# Lasersch.net
KiCad netlist of a schematic drawn in Altium Designer
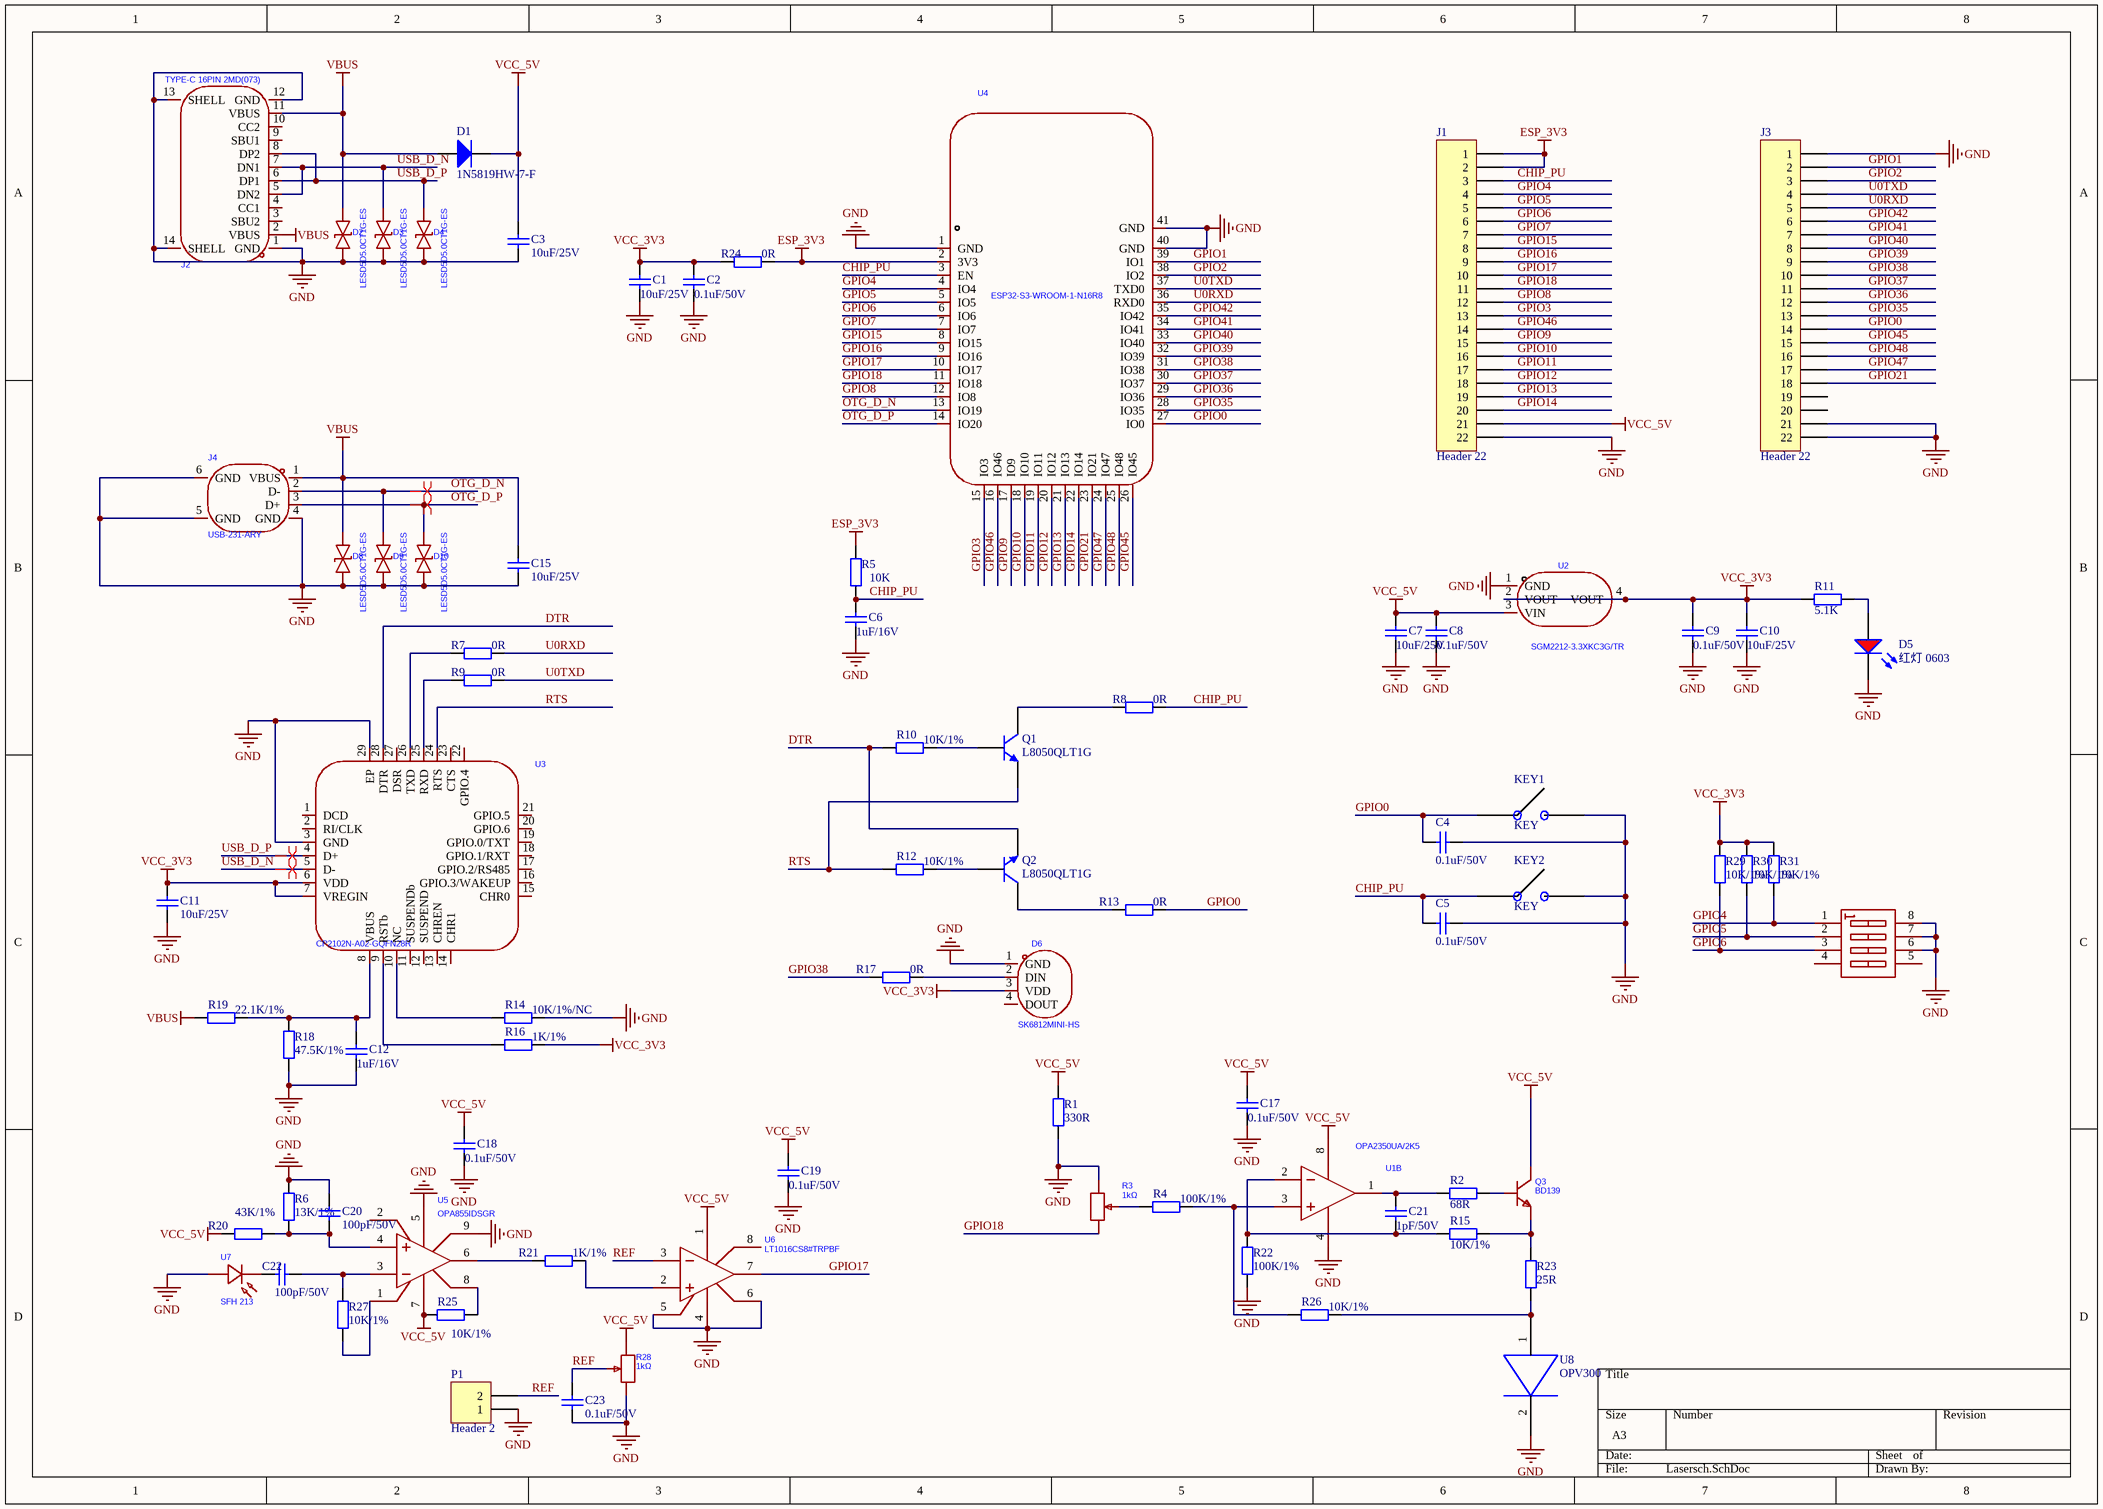
[diagram p0: Lasersch.SchDoc]

(export (version "E")
  (design (tool "Eeschema 10.0.6"))
  (components
    (comp (ref "C1")
      (value "10uF/25V")
      (footprint "0805_C")
      (description "贴片电容")
      (libsource (lib "Cap") (part "0805 2.0pF (2R0) 0.25pF 50V"))
    )
    (comp (ref "C2")
      (value "0.1uF/50V")
      (footprint "0603_C")
      (description "贴片电容")
      (libsource (lib "Cap") (part "0603 8.2nF (822) 10% 50V"))
    )
    (comp (ref "C3")
      (value "10uF/25V")
      (footprint "0805_C")
      (description "贴片电容")
      (libsource (lib "Cap") (part "0805 2.0pF (2R0) 0.25pF 50V"))
    )
    (comp (ref "C4")
      (value "0.1uF/50V")
      (footprint "0603_C")
      (description "贴片电容")
      (libsource (lib "Cap") (part "0603 8.2nF (822) 10% 50V"))
    )
    (comp (ref "C5")
      (value "0.1uF/50V")
      (footprint "0603_C")
      (description "贴片电容")
      (libsource (lib "Cap") (part "0603 8.2nF (822) 10% 50V"))
    )
    (comp (ref "C6")
      (value "1uF/16V")
      (footprint "0603_C")
      (description "贴片电容")
      (libsource (lib "Cap") (part "0603 8.2nF (822) 10% 50V"))
    )
    (comp (ref "C7")
      (value "10uF/25V")
      (footprint "0805_C")
      (description "贴片电容")
      (libsource (lib "Cap") (part "0805 2.0pF (2R0) 0.25pF 50V"))
    )
    (comp (ref "C8")
      (value "0.1uF/50V")
      (footprint "0603_C")
      (description "贴片电容")
      (libsource (lib "Cap") (part "0603 8.2nF (822) 10% 50V"))
    )
    (comp (ref "C9")
      (value "0.1uF/50V")
      (footprint "0603_C")
      (description "贴片电容")
      (libsource (lib "Cap") (part "0603 8.2nF (822) 10% 50V"))
    )
    (comp (ref "C10")
      (value "10uF/25V")
      (footprint "0805_C")
      (description "贴片电容")
      (libsource (lib "Cap") (part "0805 2.0pF (2R0) 0.25pF 50V"))
    )
    (comp (ref "C11")
      (value "10uF/25V")
      (footprint "0805_C")
      (description "贴片电容")
      (libsource (lib "Cap") (part "0805 2.0pF (2R0) 0.25pF 50V"))
    )
    (comp (ref "C12")
      (value "1uF/16V")
      (footprint "0603_C")
      (description "贴片电容")
      (libsource (lib "Cap") (part "0603 8.2nF (822) 10% 50V"))
    )
    (comp (ref "C15")
      (value "10uF/25V")
      (footprint "0805_C")
      (description "贴片电容")
      (libsource (lib "Cap") (part "0805 2.0pF (2R0) 0.25pF 50V"))
    )
    (comp (ref "C17")
      (value "0.1uF/50V")
      (footprint "0603_C")
      (description "贴片电容")
      (libsource (lib "Cap") (part "0603 8.2nF (822) 10% 50V"))
    )
    (comp (ref "C18")
      (value "0.1uF/50V")
      (footprint "0603_C")
      (description "贴片电容")
      (libsource (lib "Cap") (part "0603 8.2nF (822) 10% 50V"))
    )
    (comp (ref "C19")
      (value "0.1uF/50V")
      (footprint "0603_C")
      (description "贴片电容")
      (libsource (lib "Cap") (part "0603 8.2nF (822) 10% 50V"))
    )
    (comp (ref "C20")
      (value "100pF/50V")
      (footprint "0603_C")
      (description "贴片电容")
      (libsource (lib "Cap") (part "0603 8.2nF (822) 10% 50V"))
    )
    (comp (ref "C21")
      (value "1pF/50V")
      (footprint "0603_C")
      (description "贴片电容")
      (libsource (lib "Cap") (part "0603 8.2nF (822) 10% 50V"))
    )
    (comp (ref "C22")
      (value "100pF/50V")
      (footprint "0603_C")
      (description "贴片电容")
      (libsource (lib "Cap") (part "0603 8.2nF (822) 10% 50V"))
    )
    (comp (ref "C23")
      (value "0.1uF/50V")
      (footprint "0603_C")
      (description "贴片电容")
      (libsource (lib "Cap") (part "0603 8.2nF (822) 10% 50V"))
    )
    (comp (ref "D1")
      (value "1N5819HW-7-F")
      (footprint "SOD-123")
      (description "射频开关二极管")
      (libsource (lib "Diode") (part "1SS314"))
    )
    (comp (ref "D2")
      (value "LESD5D5.0CT1G-ES")
      (footprint "SOD-523_L1.2-W0.8-LS1.6-BI")
      (fields (field (name "MANUFACTURER") "ElecSuper(静芯微)"))
      (libsource (lib "电源板") (part "LESD5D5.0CT1G-ES"))
    )
    (comp (ref "D3")
      (value "LESD5D5.0CT1G-ES")
      (footprint "SOD-523_L1.2-W0.8-LS1.6-BI")
      (fields (field (name "MANUFACTURER") "ElecSuper(静芯微)"))
      (libsource (lib "电源板") (part "LESD5D5.0CT1G-ES"))
    )
    (comp (ref "D4")
      (value "LESD5D5.0CT1G-ES")
      (footprint "SOD-523_L1.2-W0.8-LS1.6-BI")
      (fields (field (name "MANUFACTURER") "ElecSuper(静芯微)"))
      (libsource (lib "电源板") (part "LESD5D5.0CT1G-ES"))
    )
    (comp (ref "D5")
      (value "红灯 0603")
      (footprint "0603_LED_S1")
      (description "发光二极管")
      (libsource (lib "LED") (part "0603 红灯"))
    )
    (comp (ref "D6")
      (value "SK6812MINI-HS")
      (footprint "LED-SMD_4P-L3.5-W3.5-BR_SK6812MINI-HS")
      (fields (field (name "MANUFACTURER") "欧思科光电"))
      (libsource (lib "电源板") (part "SK6812MINI-HS"))
    )
    (comp (ref "D8")
      (value "LESD5D5.0CT1G-ES")
      (footprint "SOD-523_L1.2-W0.8-LS1.6-BI")
      (fields (field (name "MANUFACTURER") "ElecSuper(静芯微)"))
      (libsource (lib "电源板") (part "LESD5D5.0CT1G-ES"))
    )
    (comp (ref "D9")
      (value "LESD5D5.0CT1G-ES")
      (footprint "SOD-523_L1.2-W0.8-LS1.6-BI")
      (fields (field (name "MANUFACTURER") "ElecSuper(静芯微)"))
      (libsource (lib "电源板") (part "LESD5D5.0CT1G-ES"))
    )
    (comp (ref "D10")
      (value "LESD5D5.0CT1G-ES")
      (footprint "SOD-523_L1.2-W0.8-LS1.6-BI")
      (fields (field (name "MANUFACTURER") "ElecSuper(静芯微)"))
      (libsource (lib "电源板") (part "LESD5D5.0CT1G-ES"))
    )
    (comp (ref "J1")
      (value "Header 22")
      (footprint "HDR1X22")
      (description "Header, 22-Pin")
      (fields (field (name "PUBLISHER") "Altium Limited"))
      (libsource (lib "Miscellaneous Connectors") (part "Header 22"))
    )
    (comp (ref "J2")
      (value "TYPE-C 16PIN 2MD(073)")
      (footprint "USB-C-SMD_TYPE-C-6PIN-2MD-073")
      (fields (field (name "MANUFACTURER") "SHOU HAN(首韩)"))
      (libsource (lib "电源板") (part "TYPE-C 16PIN 2MD(073)"))
    )
    (comp (ref "J3")
      (value "Header 22")
      (footprint "HDR1X22")
      (description "Header, 22-Pin")
      (fields (field (name "PUBLISHER") "Altium Limited"))
      (libsource (lib "Miscellaneous Connectors") (part "Header 22"))
    )
    (comp (ref "J4")
      (value "USB-231-ARY")
      (footprint "USB-A-TH_USB-231-ARY")
      (fields (field (name "MANUFACTURER") "XUNPU(讯普)"))
      (libsource (lib "电源板") (part "USB-231-ARY"))
    )
    (comp (ref "KEY1") (value "KEY") (footprint "SW-smt") (libsource (lib "My Device") (part "keysmt")))
    (comp (ref "KEY2") (value "KEY") (footprint "SW-smt") (libsource (lib "My Device") (part "keysmt")))
    (comp (ref "P1")
      (value "Header 2")
      (footprint "HDR1X2")
      (description "Header, 2-Pin")
      (fields (field (name "PUBLISHER") "Altium Limited"))
      (libsource (lib "Miscellaneous Connectors") (part "Header 2"))
    )
    (comp (ref "Q1")
      (value "L8050QLT1G")
      (footprint "SOT-23(SOT-23-3)")
      (description "三极管")
      (libsource (lib "Transistor_NPN") (part "SOT-23 MMBT5551  G1"))
    )
    (comp (ref "Q2")
      (value "L8050QLT1G")
      (footprint "SOT-23(SOT-23-3)")
      (description "三极管")
      (libsource (lib "Transistor_NPN") (part "SOT-23 MMBT5551  G1"))
    )
    (comp (ref "Q3")
      (value "BD139")
      (footprint "TO-126_L7.5-W2.5-P2.3-B")
      (fields (field (name "MANUFACTURER") "ST(意法半导体)"))
      (libsource (lib "电源板") (part "BD139"))
    )
    (comp (ref "R1")
      (value "330R")
      (footprint "0603_R")
      (description "贴片电阻")
      (libsource (lib "RES") (part "0603 1KΩ (1001) 1%"))
    )
    (comp (ref "R2")
      (value "68R")
      (footprint "0603_R")
      (description "贴片电阻")
      (libsource (lib "") (part "0603 1KΩ (1001) 1%_3"))
    )
    (comp (ref "R3")
      (value "1kΩ")
      (footprint "RES-ADJ-TH_3296W")
      (fields
        (field (name "MANUFACTURER") "BOURNS")
        (field (name "MANUFACTURER PART") "3296W-1-102LF")
        (field (name "TOLERANCE") "±10%")
      )
      (libsource (lib "电源板") (part "3296W-1-102LF"))
    )
    (comp (ref "R4")
      (value "100K/1%")
      (footprint "0603_R")
      (description "贴片电阻")
      (libsource (lib "") (part "0603 1KΩ (1001) 1%_1"))
    )
    (comp (ref "R5")
      (value "10K")
      (footprint "0603_R")
      (description "贴片电阻")
      (libsource (lib "RES") (part "0603 1KΩ (1001) 1%"))
    )
    (comp (ref "R6")
      (value "13K/1%")
      (footprint "0603_R")
      (description "贴片电阻")
      (libsource (lib "RES") (part "0603 1KΩ (1001) 1%"))
    )
    (comp (ref "R7")
      (value "0R")
      (footprint "0603_R")
      (description "贴片电阻")
      (libsource (lib "") (part "0603 1KΩ (1001) 1%_1"))
    )
    (comp (ref "R8")
      (value "0R")
      (footprint "0603_R")
      (description "贴片电阻")
      (libsource (lib "") (part "0603 1KΩ (1001) 1%_1"))
    )
    (comp (ref "R9")
      (value "0R")
      (footprint "0603_R")
      (description "贴片电阻")
      (libsource (lib "") (part "0603 1KΩ (1001) 1%_1"))
    )
    (comp (ref "R10")
      (value "10K/1%")
      (footprint "0603_R")
      (description "贴片电阻")
      (libsource (lib "") (part "0603 1KΩ (1001) 1%_1"))
    )
    (comp (ref "R11")
      (value "5.1K")
      (footprint "0603_R")
      (description "贴片电阻")
      (libsource (lib "") (part "0603 1KΩ (1001) 1%_3"))
    )
    (comp (ref "R12")
      (value "10K/1%")
      (footprint "0603_R")
      (description "贴片电阻")
      (libsource (lib "") (part "0603 1KΩ (1001) 1%_1"))
    )
    (comp (ref "R13")
      (value "0R")
      (footprint "0603_R")
      (description "贴片电阻")
      (libsource (lib "") (part "0603 1KΩ (1001) 1%_1"))
    )
    (comp (ref "R14")
      (value "10K/1%/NC")
      (footprint "0603_R")
      (description "贴片电阻")
      (libsource (lib "") (part "0603 1KΩ (1001) 1%_1"))
    )
    (comp (ref "R15")
      (value "10K/1%")
      (footprint "0603_R")
      (description "贴片电阻")
      (libsource (lib "") (part "0603 1KΩ (1001) 1%_3"))
    )
    (comp (ref "R16")
      (value "1K/1%")
      (footprint "0603_R")
      (description "贴片电阻")
      (libsource (lib "") (part "0603 1KΩ (1001) 1%_1"))
    )
    (comp (ref "R17")
      (value "0R")
      (footprint "0603_R")
      (description "贴片电阻")
      (libsource (lib "") (part "0603 1KΩ (1001) 1%_1"))
    )
    (comp (ref "R18")
      (value "47.5K/1%")
      (footprint "0603_R")
      (description "贴片电阻")
      (libsource (lib "RES") (part "0603 1KΩ (1001) 1%"))
    )
    (comp (ref "R19")
      (value "22.1K/1%")
      (footprint "0603_R")
      (description "贴片电阻")
      (libsource (lib "") (part "0603 1KΩ (1001) 1%_1"))
    )
    (comp (ref "R20")
      (value "43K/1%")
      (footprint "0603_R")
      (description "贴片电阻")
      (libsource (lib "") (part "0603 1KΩ (1001) 1%_1"))
    )
    (comp (ref "R21")
      (value "1K/1%")
      (footprint "0603_R")
      (description "贴片电阻")
      (libsource (lib "") (part "0603 1KΩ (1001) 1%_1"))
    )
    (comp (ref "R22")
      (value "100K/1%")
      (footprint "0603_R")
      (description "贴片电阻")
      (libsource (lib "") (part "0603 1KΩ (1001) 1%_2"))
    )
    (comp (ref "R23")
      (value "25R")
      (footprint "0603_R")
      (description "贴片电阻")
      (libsource (lib "") (part "0603 1KΩ (1001) 1%_2"))
    )
    (comp (ref "R24")
      (value "0R")
      (footprint "0603_R")
      (description "贴片电阻")
      (libsource (lib "") (part "0603 1KΩ (1001) 1%_1"))
    )
    (comp (ref "R25")
      (value "10K/1%")
      (footprint "0603_R")
      (description "贴片电阻")
      (libsource (lib "") (part "0603 1KΩ (1001) 1%_1"))
    )
    (comp (ref "R26")
      (value "10K/1%")
      (footprint "0603_R")
      (description "贴片电阻")
      (libsource (lib "") (part "0603 1KΩ (1001) 1%_1"))
    )
    (comp (ref "R27")
      (value "10K/1%")
      (footprint "0603_R")
      (description "贴片电阻")
      (libsource (lib "RES") (part "0603 1KΩ (1001) 1%"))
    )
    (comp (ref "R28")
      (value "1kΩ")
      (footprint "RES-ADJ-TH_3296W")
      (fields
        (field (name "MANUFACTURER") "BOURNS")
        (field (name "MANUFACTURER PART") "3296W-1-102LF")
        (field (name "TOLERANCE") "±10%")
      )
      (libsource (lib "电源板") (part "3296W-1-102LF"))
    )
    (comp (ref "R29")
      (value "10K/1%")
      (footprint "0603_R")
      (description "贴片电阻")
      (libsource (lib "RES") (part "0603 1KΩ (1001) 1%"))
    )
    (comp (ref "R30")
      (value "10K/1%")
      (footprint "0603_R")
      (description "贴片电阻")
      (libsource (lib "RES") (part "0603 1KΩ (1001) 1%"))
    )
    (comp (ref "R31")
      (value "10K/1%")
      (footprint "0603_R")
      (description "贴片电阻")
      (libsource (lib "RES") (part "0603 1KΩ (1001) 1%"))
    )
    (comp (ref "U1")
      (value "OPA2350UA/2K5")
      (footprint "SOIC-8_L4.9-W3.9-P1.27-LS6.0-BL")
      (fields (field (name "MANUFACTURER") "TI(德州仪器)"))
      (libsource (lib "电源板") (part "OPA2350UA/2K5"))
    )
    (comp (ref "U2")
      (value "SGM2212-3.3XKC3G/TR")
      (footprint "SOT-223-3_L6.5-W3.4-P2.30-LS7.0-BR")
      (fields (field (name "MANUFACTURER") "SGMICRO(圣邦微)"))
      (libsource (lib "电源板") (part "SGM2212-3.3XKC3G/TR_C3294699"))
    )
    (comp (ref "U3")
      (value "CP2102N-A02-GQFN28R")
      (footprint "QFN-28_L5.0-W5.0-P0.50-TL-EP3.3")
      (fields (field (name "MANUFACTURER") "SKYWORKS/SILICON LABS(芯科)"))
      (libsource (lib "电源板") (part "CP2102N-A02-GQFN28R"))
    )
    (comp (ref "U4")
      (value "ESP32-S3-WROOM-1-N16R8")
      (footprint "WIRELM-SMD_ESP32-S3-WROOM-1")
      (fields (field (name "MANUFACTURER") "ESPRESSIF(乐鑫)"))
      (libsource (lib "电源板") (part "ESP32-S3-WROOM-1-N16R8"))
    )
    (comp (ref "U5")
      (value "OPA855IDSGR")
      (footprint "DFN-8_L2.0-W2.0-P0.50-BL-EP")
      (fields (field (name "MANUFACTURER") "TI(德州仪器)"))
      (libsource (lib "电源板") (part "OPA855IDSGR"))
    )
    (comp (ref "U6")
      (value "LT1016CS8#TRPBF")
      (footprint "SO-8_L4.9-W3.9-P1.27-LS5.9-BL")
      (fields (field (name "MANUFACTURER") "ADI(亚德诺)"))
      (libsource (lib "电源板") (part "LT1016CS8#TRPBF"))
    )
    (comp (ref "U7")
      (value "SFH 213")
      (footprint "LED-TH_BD5.8-P2.54-RD")
      (fields (field (name "MANUFACTURER") "OSRAM(欧司朗)"))
      (libsource (lib "电源板") (part "SFH 213"))
    )
    (comp (ref "U8") (value "OPV300") (footprint "OPV300") (libsource (lib "电源板") (part "OPV300")))
    (comp (ref "U9")
      (value "BX-DS2.54-4PTP")
      (footprint "SW-SMD_8P-L10.3-W6.2-P2.54-LS9.5-BL")
      (fields (field (name "MANUFACTURER") "Bossie(博锡)"))
      (libsource (lib "电源板") (part "BX-DS2.54-4PTP"))
    )
  )
  (nets
    (net (code "1") (name "/CHIP_PU") (class "Default")
      (node (ref "C5") (pin "2") (pinfunction "2_2") (pintype "passive"))
      (node (ref "C6") (pin "2") (pinfunction "2_2") (pintype "passive"))
      (node (ref "J1") (pin "3") (pinfunction "3_3") (pintype "passive"))
      (node (ref "KEY2") (pin "1") (pinfunction "1_1") (pintype "passive"))
      (node (ref "R5") (pin "1") (pinfunction "1_1") (pintype "passive"))
      (node (ref "R8") (pin "2") (pinfunction "2_2") (pintype "passive"))
      (node (ref "U4") (pin "3") (pinfunction "EN_3") (pintype "passive"))
    )
    (net (code "2") (name "/DTR") (class "Default")
      (node (ref "Q2") (pin "2") (pinfunction "E_2") (pintype "passive"))
      (node (ref "R10") (pin "1") (pinfunction "1_1") (pintype "passive"))
      (node (ref "U3") (pin "28") (pinfunction "DTR_28") (pintype "passive"))
    )
    (net (code "3") (name "/GPIO0") (class "Default")
      (node (ref "C4") (pin "2") (pinfunction "2_2") (pintype "passive"))
      (node (ref "J3") (pin "14") (pinfunction "14_14") (pintype "passive"))
      (node (ref "KEY1") (pin "1") (pinfunction "1_1") (pintype "passive"))
      (node (ref "R13") (pin "2") (pinfunction "2_2") (pintype "passive"))
      (node (ref "U4") (pin "27") (pinfunction "IO0_27") (pintype "passive"))
    )
    (net (code "4") (name "/GPIO1") (class "Default")
      (node (ref "J3") (pin "2") (pinfunction "2_2") (pintype "passive"))
      (node (ref "U4") (pin "39") (pinfunction "IO1_39") (pintype "passive"))
    )
    (net (code "5") (name "/GPIO2") (class "Default")
      (node (ref "J3") (pin "3") (pinfunction "3_3") (pintype "passive"))
      (node (ref "U4") (pin "38") (pinfunction "IO2_38") (pintype "passive"))
    )
    (net (code "6") (name "/GPIO3") (class "Default")
      (node (ref "J1") (pin "13") (pinfunction "13_13") (pintype "passive"))
      (node (ref "U4") (pin "15") (pinfunction "IO3_15") (pintype "passive"))
    )
    (net (code "7") (name "/GPIO4") (class "Default")
      (node (ref "J1") (pin "4") (pinfunction "4_4") (pintype "passive"))
      (node (ref "R31") (pin "1") (pinfunction "1_1") (pintype "passive"))
      (node (ref "U4") (pin "4") (pinfunction "IO4_4") (pintype "passive"))
      (node (ref "U9") (pin "1") (pinfunction "1_1") (pintype "passive"))
    )
    (net (code "8") (name "/GPIO5") (class "Default")
      (node (ref "J1") (pin "5") (pinfunction "5_5") (pintype "passive"))
      (node (ref "R30") (pin "1") (pinfunction "1_1") (pintype "passive"))
      (node (ref "U4") (pin "5") (pinfunction "IO5_5") (pintype "passive"))
      (node (ref "U9") (pin "2") (pinfunction "2_2") (pintype "passive"))
    )
    (net (code "9") (name "/GPIO6") (class "Default")
      (node (ref "J1") (pin "6") (pinfunction "6_6") (pintype "passive"))
      (node (ref "R29") (pin "1") (pinfunction "1_1") (pintype "passive"))
      (node (ref "U4") (pin "6") (pinfunction "IO6_6") (pintype "passive"))
      (node (ref "U9") (pin "3") (pinfunction "3_3") (pintype "passive"))
    )
    (net (code "10") (name "/GPIO7") (class "Default")
      (node (ref "J1") (pin "7") (pinfunction "7_7") (pintype "passive"))
      (node (ref "U4") (pin "7") (pinfunction "IO7_7") (pintype "passive"))
    )
    (net (code "11") (name "/GPIO8") (class "Default")
      (node (ref "J1") (pin "12") (pinfunction "12_12") (pintype "passive"))
      (node (ref "U4") (pin "12") (pinfunction "IO8_12") (pintype "passive"))
    )
    (net (code "12") (name "/GPIO9") (class "Default")
      (node (ref "J1") (pin "15") (pinfunction "15_15") (pintype "passive"))
      (node (ref "U4") (pin "17") (pinfunction "IO9_17") (pintype "passive"))
    )
    (net (code "13") (name "/GPIO10") (class "Default")
      (node (ref "J1") (pin "16") (pinfunction "16_16") (pintype "passive"))
      (node (ref "U4") (pin "18") (pinfunction "IO10_18") (pintype "passive"))
    )
    (net (code "14") (name "/GPIO11") (class "Default")
      (node (ref "J1") (pin "17") (pinfunction "17_17") (pintype "passive"))
      (node (ref "U4") (pin "19") (pinfunction "IO11_19") (pintype "passive"))
    )
    (net (code "15") (name "/GPIO12") (class "Default")
      (node (ref "J1") (pin "18") (pinfunction "18_18") (pintype "passive"))
      (node (ref "U4") (pin "20") (pinfunction "IO12_20") (pintype "passive"))
    )
    (net (code "16") (name "/GPIO13") (class "Default")
      (node (ref "J1") (pin "19") (pinfunction "19_19") (pintype "passive"))
      (node (ref "U4") (pin "21") (pinfunction "IO13_21") (pintype "passive"))
    )
    (net (code "17") (name "/GPIO14") (class "Default")
      (node (ref "J1") (pin "20") (pinfunction "20_20") (pintype "passive"))
      (node (ref "U4") (pin "22") (pinfunction "IO14_22") (pintype "passive"))
    )
    (net (code "18") (name "/GPIO15") (class "Default")
      (node (ref "J1") (pin "8") (pinfunction "8_8") (pintype "passive"))
      (node (ref "U4") (pin "8") (pinfunction "IO15_8") (pintype "passive"))
    )
    (net (code "19") (name "/GPIO16") (class "Default")
      (node (ref "J1") (pin "9") (pinfunction "9_9") (pintype "passive"))
      (node (ref "U4") (pin "9") (pinfunction "IO16_9") (pintype "passive"))
    )
    (net (code "20") (name "/GPIO17") (class "Default")
      (node (ref "J1") (pin "10") (pinfunction "10_10") (pintype "passive"))
      (node (ref "U4") (pin "10") (pinfunction "IO17_10") (pintype "passive"))
      (node (ref "U6") (pin "7") (pinfunction "Q_OUT_7") (pintype "passive"))
    )
    (net (code "21") (name "/GPIO18") (class "Default")
      (node (ref "J1") (pin "11") (pinfunction "11_11") (pintype "passive"))
      (node (ref "R3") (pin "1") (pinfunction "1_1") (pintype "passive"))
      (node (ref "U4") (pin "11") (pinfunction "IO18_11") (pintype "passive"))
    )
    (net (code "22") (name "/GPIO21") (class "Default")
      (node (ref "J3") (pin "18") (pinfunction "18_18") (pintype "passive"))
      (node (ref "U4") (pin "23") (pinfunction "IO21_23") (pintype "passive"))
    )
    (net (code "23") (name "/GPIO35") (class "Default")
      (node (ref "J3") (pin "13") (pinfunction "13_13") (pintype "passive"))
      (node (ref "U4") (pin "28") (pinfunction "IO35_28") (pintype "passive"))
    )
    (net (code "24") (name "/GPIO36") (class "Default")
      (node (ref "J3") (pin "12") (pinfunction "12_12") (pintype "passive"))
      (node (ref "U4") (pin "29") (pinfunction "IO36_29") (pintype "passive"))
    )
    (net (code "25") (name "/GPIO37") (class "Default")
      (node (ref "J3") (pin "11") (pinfunction "11_11") (pintype "passive"))
      (node (ref "U4") (pin "30") (pinfunction "IO37_30") (pintype "passive"))
    )
    (net (code "26") (name "/GPIO38") (class "Default")
      (node (ref "J3") (pin "10") (pinfunction "10_10") (pintype "passive"))
      (node (ref "R17") (pin "1") (pinfunction "1_1") (pintype "passive"))
      (node (ref "U4") (pin "31") (pinfunction "IO38_31") (pintype "passive"))
    )
    (net (code "27") (name "/GPIO39") (class "Default")
      (node (ref "J3") (pin "9") (pinfunction "9_9") (pintype "passive"))
      (node (ref "U4") (pin "32") (pinfunction "IO39_32") (pintype "passive"))
    )
    (net (code "28") (name "/GPIO40") (class "Default")
      (node (ref "J3") (pin "8") (pinfunction "8_8") (pintype "passive"))
      (node (ref "U4") (pin "33") (pinfunction "IO40_33") (pintype "passive"))
    )
    (net (code "29") (name "/GPIO41") (class "Default")
      (node (ref "J3") (pin "7") (pinfunction "7_7") (pintype "passive"))
      (node (ref "U4") (pin "34") (pinfunction "IO41_34") (pintype "passive"))
    )
    (net (code "30") (name "/GPIO42") (class "Default")
      (node (ref "J3") (pin "6") (pinfunction "6_6") (pintype "passive"))
      (node (ref "U4") (pin "35") (pinfunction "IO42_35") (pintype "passive"))
    )
    (net (code "31") (name "/GPIO45") (class "Default")
      (node (ref "J3") (pin "15") (pinfunction "15_15") (pintype "passive"))
      (node (ref "U4") (pin "26") (pinfunction "IO45_26") (pintype "passive"))
    )
    (net (code "32") (name "/GPIO46") (class "Default")
      (node (ref "J1") (pin "14") (pinfunction "14_14") (pintype "passive"))
      (node (ref "U4") (pin "16") (pinfunction "IO46_16") (pintype "passive"))
    )
    (net (code "33") (name "/GPIO47") (class "Default")
      (node (ref "J3") (pin "17") (pinfunction "17_17") (pintype "passive"))
      (node (ref "U4") (pin "24") (pinfunction "IO47_24") (pintype "passive"))
    )
    (net (code "34") (name "/GPIO48") (class "Default")
      (node (ref "J3") (pin "16") (pinfunction "16_16") (pintype "passive"))
      (node (ref "U4") (pin "25") (pinfunction "IO48_25") (pintype "passive"))
    )
    (net (code "35") (name "/OTG_D_N") (class "Default")
      (node (ref "D9") (pin "2") (pinfunction "2_2") (pintype "passive"))
      (node (ref "J4") (pin "2") (pinfunction "D-_2") (pintype "passive"))
      (node (ref "U4") (pin "13") (pinfunction "IO19_13") (pintype "passive"))
    )
    (net (code "36") (name "/OTG_D_P") (class "Default")
      (node (ref "D10") (pin "2") (pinfunction "2_2") (pintype "passive"))
      (node (ref "J4") (pin "3") (pinfunction "D+_3") (pintype "passive"))
      (node (ref "U4") (pin "14") (pinfunction "IO20_14") (pintype "passive"))
    )
    (net (code "37") (name "/REF") (class "Default")
      (node (ref "C23") (pin "1") (pinfunction "1_1") (pintype "passive"))
      (node (ref "P1") (pin "2") (pinfunction "2_2") (pintype "passive"))
      (node (ref "R28") (pin "2") (pinfunction "2_2") (pintype "passive"))
      (node (ref "U6") (pin "3") (pinfunction "IN-_3") (pintype "passive"))
    )
    (net (code "38") (name "/RTS") (class "Default")
      (node (ref "Q1") (pin "2") (pinfunction "E_2") (pintype "passive"))
      (node (ref "R12") (pin "1") (pinfunction "1_1") (pintype "passive"))
      (node (ref "U3") (pin "24") (pinfunction "RTS_24") (pintype "passive"))
    )
    (net (code "39") (name "/U0RXD") (class "Default")
      (node (ref "J3") (pin "5") (pinfunction "5_5") (pintype "passive"))
      (node (ref "R7") (pin "2") (pinfunction "2_2") (pintype "passive"))
      (node (ref "U4") (pin "36") (pinfunction "RXD0_36") (pintype "passive"))
    )
    (net (code "40") (name "/U0TXD") (class "Default")
      (node (ref "J3") (pin "4") (pinfunction "4_4") (pintype "passive"))
      (node (ref "R9") (pin "2") (pinfunction "2_2") (pintype "passive"))
      (node (ref "U4") (pin "37") (pinfunction "TXD0_37") (pintype "passive"))
    )
    (net (code "41") (name "/USB_D_N") (class "Default")
      (node (ref "D3") (pin "2") (pinfunction "2_2") (pintype "passive"))
      (node (ref "J2") (pin "5") (pinfunction "DN2_5") (pintype "passive"))
      (node (ref "J2") (pin "7") (pinfunction "DN1_7") (pintype "passive"))
      (node (ref "U3") (pin "5") (pinfunction "D-_5") (pintype "passive"))
    )
    (net (code "42") (name "/USB_D_P") (class "Default")
      (node (ref "D4") (pin "2") (pinfunction "2_2") (pintype "passive"))
      (node (ref "J2") (pin "6") (pinfunction "DP1_6") (pintype "passive"))
      (node (ref "J2") (pin "8") (pinfunction "DP2_8") (pintype "passive"))
      (node (ref "U3") (pin "4") (pinfunction "D+_4") (pintype "passive"))
    )
    (net (code "43") (name "ESP_3V3") (class "Default")
      (node (ref "J1") (pin "1") (pinfunction "1_1") (pintype "passive"))
      (node (ref "J1") (pin "2") (pinfunction "2_2") (pintype "passive"))
      (node (ref "R24") (pin "2") (pinfunction "2_2") (pintype "passive"))
      (node (ref "R5") (pin "2") (pinfunction "2_2") (pintype "passive"))
      (node (ref "U4") (pin "2") (pinfunction "3V3_2") (pintype "passive"))
    )
    (net (code "44") (name "GND") (class "Default")
      (node (ref "C1") (pin "1") (pinfunction "1_1") (pintype "passive"))
      (node (ref "C10") (pin "1") (pinfunction "1_1") (pintype "passive"))
      (node (ref "C11") (pin "1") (pinfunction "1_1") (pintype "passive"))
      (node (ref "C12") (pin "1") (pinfunction "1_1") (pintype "passive"))
      (node (ref "C15") (pin "1") (pinfunction "1_1") (pintype "passive"))
      (node (ref "C17") (pin "1") (pinfunction "1_1") (pintype "passive"))
      (node (ref "C18") (pin "1") (pinfunction "1_1") (pintype "passive"))
      (node (ref "C19") (pin "1") (pinfunction "1_1") (pintype "passive"))
      (node (ref "C2") (pin "1") (pinfunction "1_1") (pintype "passive"))
      (node (ref "C20") (pin "1") (pinfunction "1_1") (pintype "passive"))
      (node (ref "C23") (pin "2") (pinfunction "2_2") (pintype "passive"))
      (node (ref "C3") (pin "1") (pinfunction "1_1") (pintype "passive"))
      (node (ref "C4") (pin "1") (pinfunction "1_1") (pintype "passive"))
      (node (ref "C5") (pin "1") (pinfunction "1_1") (pintype "passive"))
      (node (ref "C6") (pin "1") (pinfunction "1_1") (pintype "passive"))
      (node (ref "C7") (pin "1") (pinfunction "1_1") (pintype "passive"))
      (node (ref "C8") (pin "1") (pinfunction "1_1") (pintype "passive"))
      (node (ref "C9") (pin "1") (pinfunction "1_1") (pintype "passive"))
      (node (ref "D10") (pin "1") (pinfunction "1_1") (pintype "passive"))
      (node (ref "D2") (pin "1") (pinfunction "1_1") (pintype "passive"))
      (node (ref "D3") (pin "1") (pinfunction "1_1") (pintype "passive"))
      (node (ref "D4") (pin "1") (pinfunction "1_1") (pintype "passive"))
      (node (ref "D5") (pin "K") (pinfunction "K_K") (pintype "passive"))
      (node (ref "D6") (pin "1") (pinfunction "GND_1") (pintype "passive"))
      (node (ref "D8") (pin "1") (pinfunction "1_1") (pintype "passive"))
      (node (ref "D9") (pin "1") (pinfunction "1_1") (pintype "passive"))
      (node (ref "J1") (pin "22") (pinfunction "22_22") (pintype "passive"))
      (node (ref "J2") (pin "1") (pinfunction "GND_1") (pintype "passive"))
      (node (ref "J2") (pin "12") (pinfunction "GND_12") (pintype "passive"))
      (node (ref "J2") (pin "13") (pinfunction "SHELL_13") (pintype "passive"))
      (node (ref "J2") (pin "14") (pinfunction "SHELL_14") (pintype "passive"))
      (node (ref "J3") (pin "1") (pinfunction "1_1") (pintype "passive"))
      (node (ref "J3") (pin "21") (pinfunction "21_21") (pintype "passive"))
      (node (ref "J3") (pin "22") (pinfunction "22_22") (pintype "passive"))
      (node (ref "J4") (pin "4") (pinfunction "GND_4") (pintype "passive"))
      (node (ref "J4") (pin "5") (pinfunction "GND_5") (pintype "passive"))
      (node (ref "J4") (pin "6") (pinfunction "GND_6") (pintype "passive"))
      (node (ref "KEY1") (pin "2") (pinfunction "2_2") (pintype "passive"))
      (node (ref "KEY2") (pin "2") (pinfunction "2_2") (pintype "passive"))
      (node (ref "P1") (pin "1") (pinfunction "1_1") (pintype "passive"))
      (node (ref "R1") (pin "1") (pinfunction "1_1") (pintype "passive"))
      (node (ref "R14") (pin "2") (pinfunction "2_2") (pintype "passive"))
      (node (ref "R18") (pin "1") (pinfunction "1_1") (pintype "passive"))
      (node (ref "R22") (pin "2") (pinfunction "2_2") (pintype "passive"))
      (node (ref "R28") (pin "3") (pinfunction "3_3") (pintype "passive"))
      (node (ref "R3") (pin "3") (pinfunction "3_3") (pintype "passive"))
      (node (ref "R6") (pin "2") (pinfunction "2_2") (pintype "passive"))
      (node (ref "U1") (pin "4") (pinfunction "V-_4") (pintype "passive"))
      (node (ref "U2") (pin "1") (pinfunction "GND_1") (pintype "passive"))
      (node (ref "U3") (pin "29") (pinfunction "EP_29") (pintype "passive"))
      (node (ref "U3") (pin "3") (pinfunction "GND_3") (pintype "passive"))
      (node (ref "U4") (pin "1") (pinfunction "GND_1") (pintype "passive"))
      (node (ref "U4") (pin "40") (pinfunction "GND_40") (pintype "passive"))
      (node (ref "U4") (pin "41") (pinfunction "GND_41") (pintype "passive"))
      (node (ref "U5") (pin "5") (pinfunction "V-_5") (pintype "passive"))
      (node (ref "U5") (pin "9") (pinfunction "EP_9") (pintype "passive"))
      (node (ref "U6") (pin "4") (pinfunction "V-_4") (pintype "passive"))
      (node (ref "U6") (pin "5") (pinfunction "LATCH_ENABLE_5") (pintype "passive"))
      (node (ref "U6") (pin "6") (pinfunction "GND_6") (pintype "passive"))
      (node (ref "U7") (pin "2") (pinfunction "A_2") (pintype "passive"))
      (node (ref "U8") (pin "2") (pinfunction "2_2") (pintype "passive"))
      (node (ref "U9") (pin "6") (pinfunction "6_6") (pintype "passive"))
      (node (ref "U9") (pin "7") (pinfunction "7_7") (pintype "passive"))
      (node (ref "U9") (pin "8") (pinfunction "8_8") (pintype "passive"))
    )
    (net (code "45") (name "Net-(D5-PadA)") (class "Default")
      (node (ref "D5") (pin "A") (pinfunction "A_A") (pintype "passive"))
      (node (ref "R11") (pin "1") (pinfunction "1_1") (pintype "passive"))
    )
    (net (code "46") (name "Net-(D6-DIN)") (class "Default")
      (node (ref "D6") (pin "2") (pinfunction "DIN_2") (pintype "passive"))
      (node (ref "R17") (pin "2") (pinfunction "2_2") (pintype "passive"))
    )
    (net (code "47") (name "Net-(Q1-B)") (class "Default")
      (node (ref "Q1") (pin "1") (pinfunction "B_1") (pintype "passive"))
      (node (ref "R10") (pin "2") (pinfunction "2_2") (pintype "passive"))
    )
    (net (code "48") (name "Net-(Q1-C)") (class "Default")
      (node (ref "Q1") (pin "3") (pinfunction "C_3") (pintype "passive"))
      (node (ref "R8") (pin "1") (pinfunction "1_1") (pintype "passive"))
    )
    (net (code "49") (name "Net-(Q2-B)") (class "Default")
      (node (ref "Q2") (pin "1") (pinfunction "B_1") (pintype "passive"))
      (node (ref "R12") (pin "2") (pinfunction "2_2") (pintype "passive"))
    )
    (net (code "50") (name "Net-(Q2-C)") (class "Default")
      (node (ref "Q2") (pin "3") (pinfunction "C_3") (pintype "passive"))
      (node (ref "R13") (pin "1") (pinfunction "1_1") (pintype "passive"))
    )
    (net (code "51") (name "Net-(Q3-B)") (class "Default")
      (node (ref "Q3") (pin "1") (pinfunction "B_1") (pintype "passive"))
      (node (ref "R2") (pin "1") (pinfunction "1_1") (pintype "passive"))
    )
    (net (code "52") (name "Net-(Q3-E)") (class "Default")
      (node (ref "Q3") (pin "3") (pinfunction "E_3") (pintype "passive"))
      (node (ref "R15") (pin "1") (pinfunction "1_1") (pintype "passive"))
      (node (ref "R23") (pin "1") (pinfunction "1_1") (pintype "passive"))
    )
    (net (code "53") (name "Net-(R3-Pad2)") (class "Default")
      (node (ref "R3") (pin "2") (pinfunction "2_2") (pintype "passive"))
      (node (ref "R4") (pin "1") (pinfunction "1_1") (pintype "passive"))
    )
    (net (code "54") (name "Net-(R23-Pad2)") (class "Default")
      (node (ref "R23") (pin "2") (pinfunction "2_2") (pintype "passive"))
      (node (ref "R26") (pin "2") (pinfunction "2_2") (pintype "passive"))
      (node (ref "U8") (pin "1") (pinfunction "1_1") (pintype "passive"))
    )
    (net (code "55") (name "Net-(U1B-IN_A+)") (class "Default")
      (node (ref "R26") (pin "1") (pinfunction "1_1") (pintype "passive"))
      (node (ref "R4") (pin "2") (pinfunction "2_2") (pintype "passive"))
      (node (ref "U1") (pin "3") (pinfunction "IN_A+_3") (pintype "passive"))
    )
    (net (code "56") (name "Net-(U1B-IN_A-)") (class "Default")
      (node (ref "C21") (pin "1") (pinfunction "1_1") (pintype "passive"))
      (node (ref "R15") (pin "2") (pinfunction "2_2") (pintype "passive"))
      (node (ref "R22") (pin "1") (pinfunction "1_1") (pintype "passive"))
      (node (ref "U1") (pin "2") (pinfunction "IN_A-_2") (pintype "passive"))
    )
    (net (code "57") (name "Net-(U1B-OUT_A)") (class "Default")
      (node (ref "C21") (pin "2") (pinfunction "2_2") (pintype "passive"))
      (node (ref "R2") (pin "2") (pinfunction "2_2") (pintype "passive"))
      (node (ref "U1") (pin "1") (pinfunction "OUT_A_1") (pintype "passive"))
    )
    (net (code "58") (name "Net-(U3-NC)") (class "Default")
      (node (ref "R14") (pin "1") (pinfunction "1_1") (pintype "passive"))
      (node (ref "U3") (pin "10") (pinfunction "NC_10") (pintype "passive"))
    )
    (net (code "59") (name "Net-(U3-RSTb)") (class "Default")
      (node (ref "R16") (pin "1") (pinfunction "1_1") (pintype "passive"))
      (node (ref "U3") (pin "9") (pinfunction "RSTb_9") (pintype "passive"))
    )
    (net (code "60") (name "Net-(U3-RXD)") (class "Default")
      (node (ref "R9") (pin "1") (pinfunction "1_1") (pintype "passive"))
      (node (ref "U3") (pin "25") (pinfunction "RXD_25") (pintype "passive"))
    )
    (net (code "61") (name "Net-(U3-TXD)") (class "Default")
      (node (ref "R7") (pin "1") (pinfunction "1_1") (pintype "passive"))
      (node (ref "U3") (pin "26") (pinfunction "TXD_26") (pintype "passive"))
    )
    (net (code "62") (name "Net-(U3-VBUS)") (class "Default")
      (node (ref "C12") (pin "2") (pinfunction "2_2") (pintype "passive"))
      (node (ref "R18") (pin "2") (pinfunction "2_2") (pintype "passive"))
      (node (ref "R19") (pin "2") (pinfunction "2_2") (pintype "passive"))
      (node (ref "U3") (pin "8") (pinfunction "VBUS_8") (pintype "passive"))
    )
    (net (code "63") (name "Net-(U5-FB)") (class "Default")
      (node (ref "R27") (pin "1") (pinfunction "1_1") (pintype "passive"))
      (node (ref "U5") (pin "1") (pinfunction "FB_1") (pintype "passive"))
    )
    (net (code "64") (name "Net-(U5-IN+)") (class "Default")
      (node (ref "C20") (pin "2") (pinfunction "2_2") (pintype "passive"))
      (node (ref "R20") (pin "2") (pinfunction "2_2") (pintype "passive"))
      (node (ref "R6") (pin "1") (pinfunction "1_1") (pintype "passive"))
      (node (ref "U5") (pin "4") (pinfunction "IN+_4") (pintype "passive"))
    )
    (net (code "65") (name "Net-(U5-IN-)") (class "Default")
      (node (ref "C22") (pin "1") (pinfunction "1_1") (pintype "passive"))
      (node (ref "R27") (pin "2") (pinfunction "2_2") (pintype "passive"))
      (node (ref "U5") (pin "3") (pinfunction "IN-_3") (pintype "passive"))
    )
    (net (code "66") (name "Net-(U5-PD#)") (class "Default")
      (node (ref "R25") (pin "2") (pinfunction "2_2") (pintype "passive"))
      (node (ref "U5") (pin "8") (pinfunction "PD#_8") (pintype "passive"))
    )
    (net (code "67") (name "Net-(U5-VOUT)") (class "Default")
      (node (ref "R21") (pin "1") (pinfunction "1_1") (pintype "passive"))
      (node (ref "U5") (pin "6") (pinfunction "VOUT_6") (pintype "passive"))
    )
    (net (code "68") (name "Net-(U6-IN+)") (class "Default")
      (node (ref "R21") (pin "2") (pinfunction "2_2") (pintype "passive"))
      (node (ref "U6") (pin "2") (pinfunction "IN+_2") (pintype "passive"))
    )
    (net (code "69") (name "Net-(U7-K)") (class "Default")
      (node (ref "C22") (pin "2") (pinfunction "2_2") (pintype "passive"))
      (node (ref "U7") (pin "1") (pinfunction "K_1") (pintype "passive"))
    )
    (net (code "70") (name "VBUS") (class "Default")
      (node (ref "C15") (pin "2") (pinfunction "2_2") (pintype "passive"))
      (node (ref "D1") (pin "1") (pinfunction "A_1") (pintype "passive"))
      (node (ref "D2") (pin "2") (pinfunction "2_2") (pintype "passive"))
      (node (ref "D8") (pin "2") (pinfunction "2_2") (pintype "passive"))
      (node (ref "J2") (pin "11") (pinfunction "VBUS_11") (pintype "passive"))
      (node (ref "J2") (pin "2") (pinfunction "VBUS_2") (pintype "passive"))
      (node (ref "J4") (pin "1") (pinfunction "VBUS_1") (pintype "passive"))
      (node (ref "R19") (pin "1") (pinfunction "1_1") (pintype "passive"))
    )
    (net (code "71") (name "VCC_3V3") (class "Default")
      (node (ref "C1") (pin "2") (pinfunction "2_2") (pintype "passive"))
      (node (ref "C10") (pin "2") (pinfunction "2_2") (pintype "passive"))
      (node (ref "C11") (pin "2") (pinfunction "2_2") (pintype "passive"))
      (node (ref "C2") (pin "2") (pinfunction "2_2") (pintype "passive"))
      (node (ref "C9") (pin "2") (pinfunction "2_2") (pintype "passive"))
      (node (ref "D6") (pin "3") (pinfunction "VDD_3") (pintype "passive"))
      (node (ref "R11") (pin "2") (pinfunction "2_2") (pintype "passive"))
      (node (ref "R16") (pin "2") (pinfunction "2_2") (pintype "passive"))
      (node (ref "R24") (pin "1") (pinfunction "1_1") (pintype "passive"))
      (node (ref "R29") (pin "2") (pinfunction "2_2") (pintype "passive"))
      (node (ref "R30") (pin "2") (pinfunction "2_2") (pintype "passive"))
      (node (ref "R31") (pin "2") (pinfunction "2_2") (pintype "passive"))
      (node (ref "U2") (pin "2") (pinfunction "VOUT_2") (pintype "passive"))
      (node (ref "U2") (pin "4") (pinfunction "VOUT_4") (pintype "passive"))
      (node (ref "U3") (pin "6") (pinfunction "VDD_6") (pintype "passive"))
      (node (ref "U3") (pin "7") (pinfunction "VREGIN_7") (pintype "passive"))
    )
    (net (code "72") (name "VCC_5V") (class "Default")
      (node (ref "C17") (pin "2") (pinfunction "2_2") (pintype "passive"))
      (node (ref "C18") (pin "2") (pinfunction "2_2") (pintype "passive"))
      (node (ref "C19") (pin "2") (pinfunction "2_2") (pintype "passive"))
      (node (ref "C3") (pin "2") (pinfunction "2_2") (pintype "passive"))
      (node (ref "C7") (pin "2") (pinfunction "2_2") (pintype "passive"))
      (node (ref "C8") (pin "2") (pinfunction "2_2") (pintype "passive"))
      (node (ref "D1") (pin "2") (pinfunction "K_2") (pintype "passive"))
      (node (ref "J1") (pin "21") (pinfunction "21_21") (pintype "passive"))
      (node (ref "Q3") (pin "2") (pinfunction "C_2") (pintype "passive"))
      (node (ref "R1") (pin "2") (pinfunction "2_2") (pintype "passive"))
      (node (ref "R20") (pin "1") (pinfunction "1_1") (pintype "passive"))
      (node (ref "R25") (pin "1") (pinfunction "1_1") (pintype "passive"))
      (node (ref "R28") (pin "1") (pinfunction "1_1") (pintype "passive"))
      (node (ref "U1") (pin "8") (pinfunction "V+_8") (pintype "passive"))
      (node (ref "U2") (pin "3") (pinfunction "VIN_3") (pintype "passive"))
      (node (ref "U5") (pin "7") (pinfunction "V+_7") (pintype "passive"))
      (node (ref "U6") (pin "1") (pinfunction "V+_1") (pintype "passive"))
    )
    (net (code "73") (name "unconnected-(D6-DOUT-Pad4)") (class "Default")
      (node (ref "D6") (pin "4") (pinfunction "DOUT_4") (pintype "passive"))
    )
    (net (code "74") (name "unconnected-(J2-CC1-Pad4)") (class "Default")
      (node (ref "J2") (pin "4") (pinfunction "CC1_4") (pintype "passive"))
    )
    (net (code "75") (name "unconnected-(J2-CC2-Pad10)") (class "Default")
      (node (ref "J2") (pin "10") (pinfunction "CC2_10") (pintype "passive"))
    )
    (net (code "76") (name "unconnected-(J2-SBU1-Pad9)") (class "Default")
      (node (ref "J2") (pin "9") (pinfunction "SBU1_9") (pintype "passive"))
    )
    (net (code "77") (name "unconnected-(J2-SBU2-Pad3)") (class "Default")
      (node (ref "J2") (pin "3") (pinfunction "SBU2_3") (pintype "passive"))
    )
    (net (code "78") (name "unconnected-(J3-Pad19)") (class "Default")
      (node (ref "J3") (pin "19") (pinfunction "19_19") (pintype "passive"))
    )
    (net (code "79") (name "unconnected-(J3-Pad20)") (class "Default")
      (node (ref "J3") (pin "20") (pinfunction "20_20") (pintype "passive"))
    )
    (net (code "80") (name "unconnected-(U3-CHR0-Pad15)") (class "Default")
      (node (ref "U3") (pin "15") (pinfunction "CHR0_15") (pintype "passive"))
    )
    (net (code "81") (name "unconnected-(U3-CHR1-Pad14)") (class "Default")
      (node (ref "U3") (pin "14") (pinfunction "CHR1_14") (pintype "passive"))
    )
    (net (code "82") (name "unconnected-(U3-CHREN-Pad13)") (class "Default")
      (node (ref "U3") (pin "13") (pinfunction "CHREN_13") (pintype "passive"))
    )
    (net (code "83") (name "unconnected-(U3-CTS-Pad23)") (class "Default")
      (node (ref "U3") (pin "23") (pinfunction "CTS_23") (pintype "passive"))
    )
    (net (code "84") (name "unconnected-(U3-DCD-Pad1)") (class "Default")
      (node (ref "U3") (pin "1") (pinfunction "DCD_1") (pintype "passive"))
    )
    (net (code "85") (name "unconnected-(U3-DSR-Pad27)") (class "Default")
      (node (ref "U3") (pin "27") (pinfunction "DSR_27") (pintype "passive"))
    )
    (net (code "86") (name "unconnected-(U3-GPIO.0{slash}TXT-Pad19)") (class "Default")
      (node (ref "U3") (pin "19") (pinfunction "GPIO.0/TXT_19") (pintype "passive"))
    )
    (net (code "87") (name "unconnected-(U3-GPIO.1{slash}RXT-Pad18)") (class "Default")
      (node (ref "U3") (pin "18") (pinfunction "GPIO.1/RXT_18") (pintype "passive"))
    )
    (net (code "88") (name "unconnected-(U3-GPIO.2{slash}RS485-Pad17)") (class "Default")
      (node (ref "U3") (pin "17") (pinfunction "GPIO.2/RS485_17") (pintype "passive"))
    )
    (net (code "89") (name "unconnected-(U3-GPIO.3{slash}WAKEUP-Pad16)") (class "Default")
      (node (ref "U3") (pin "16") (pinfunction "GPIO.3/WAKEUP_16") (pintype "passive"))
    )
    (net (code "90") (name "unconnected-(U3-GPIO.4-Pad22)") (class "Default")
      (node (ref "U3") (pin "22") (pinfunction "GPIO.4_22") (pintype "passive"))
    )
    (net (code "91") (name "unconnected-(U3-GPIO.5-Pad21)") (class "Default")
      (node (ref "U3") (pin "21") (pinfunction "GPIO.5_21") (pintype "passive"))
    )
    (net (code "92") (name "unconnected-(U3-GPIO.6-Pad20)") (class "Default")
      (node (ref "U3") (pin "20") (pinfunction "GPIO.6_20") (pintype "passive"))
    )
    (net (code "93") (name "unconnected-(U3-RI{slash}CLK-Pad2)") (class "Default")
      (node (ref "U3") (pin "2") (pinfunction "RI/CLK_2") (pintype "passive"))
    )
    (net (code "94") (name "unconnected-(U3-SUSPEND-Pad12)") (class "Default")
      (node (ref "U3") (pin "12") (pinfunction "SUSPEND_12") (pintype "passive"))
    )
    (net (code "95") (name "unconnected-(U3-SUSPENDb-Pad11)") (class "Default")
      (node (ref "U3") (pin "11") (pinfunction "SUSPENDb_11") (pintype "passive"))
    )
    (net (code "96") (name "unconnected-(U5-NC-Pad2)") (class "Default")
      (node (ref "U5") (pin "2") (pinfunction "NC_2") (pintype "passive"))
    )
    (net (code "97") (name "unconnected-(U6-Q_OUT#-Pad8)") (class "Default")
      (node (ref "U6") (pin "8") (pinfunction "Q_OUT#_8") (pintype "passive"))
    )
    (net (code "98") (name "unconnected-(U9-Pad4)") (class "Default")
      (node (ref "U9") (pin "4") (pinfunction "4_4") (pintype "passive"))
    )
    (net (code "99") (name "unconnected-(U9-Pad5)") (class "Default")
      (node (ref "U9") (pin "5") (pinfunction "5_5") (pintype "passive"))
    )
  )
)
